# RF_Antenna_Power.net
KiCad netlist of a schematic drawn in Altium Designer
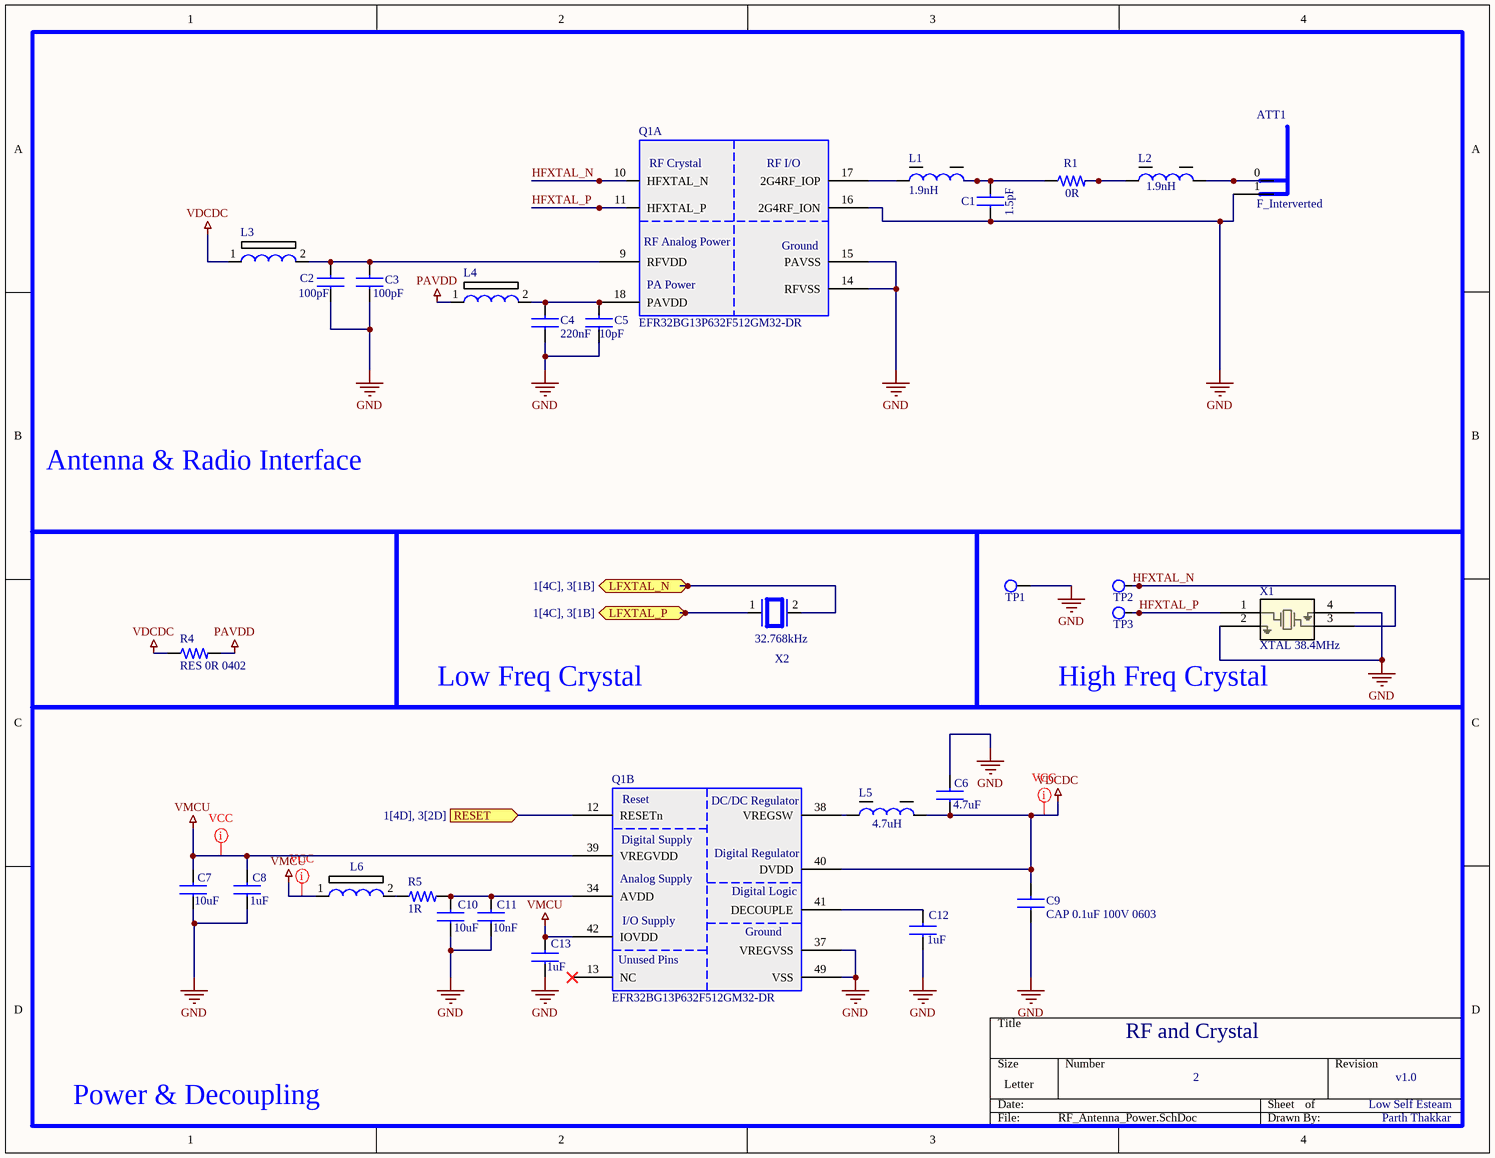
[diagram p0: RF_Antenna_Power.SchDoc]

(export (version "E")
  (design (tool "Eeschema 10.0.6"))
  (components
    (comp (ref "ATT1")
      (value "F_Interverted")
      (footprint "F_Inverted")
      (description "For 50Ohm impedence, Inverted F antenna")
      (libsource (lib "Keyboard_parts") (part "F_Interverted"))
    )
    (comp (ref "C1")
      (value "1.5pF")
      (footprint "Capacitor 0402")
      (fields
        (field (name "MANUFACTURER") "Murata")
        (field (name "MANUFACTURER PART NUMBER") "GJM1555C1H1R5WB01D")
        (field (name "Comment") "CAP 1.5pF 50V 0402")
      )
      (libsource (lib "Keyboard_parts") (part "CAP 1.5pF 50V 0402"))
    )
    (comp (ref "C2")
      (value "100pF")
      (footprint "Capacitor 0603")
      (fields
        (field (name "MANUFACTURER") "Murata")
        (field (name "MANUFACTURER PART NUMBER") "GCM1885C2A101JA16D")
        (field (name "Comment") "CAP 100pF 100V 0603")
      )
      (libsource (lib "Keyboard_parts") (part "CAP 100pF 100V 0603"))
    )
    (comp (ref "C3")
      (value "100pF")
      (footprint "Capacitor 0603")
      (fields
        (field (name "MANUFACTURER") "Murata")
        (field (name "MANUFACTURER PART NUMBER") "GCM1885C2A101JA16D")
        (field (name "Comment") "CAP 100pF 100V 0603")
      )
      (libsource (lib "Keyboard_parts") (part "CAP 100pF 100V 0603"))
    )
    (comp (ref "C4")
      (value "220nF")
      (footprint "Capacitor 0603")
      (fields
        (field (name "MANUFACTURER") "Murata")
        (field (name "MANUFACTURER PART NUMBER") "GRM188R71H224KAC4D")
        (field (name "Comment") "CAP 220nF 50V 0603")
      )
      (libsource (lib "Keyboard_parts") (part "CAP 220nF 50V 0603"))
    )
    (comp (ref "C5")
      (value "10pF")
      (footprint "Capacitor 0603")
      (fields
        (field (name "MANUFACTURER") "Murata")
        (field (name "MANUFACTURER PART NUMBER") "GRM1555C1H100FA01D")
        (field (name "Comment") "CAP 10pF 50V 0603")
      )
      (libsource (lib "Keyboard_parts") (part "CAP 10pF 50V 0603"))
    )
    (comp (ref "C6")
      (value "4.7uF")
      (footprint "Capacitor 0603")
      (fields
        (field (name "MANUFACTURER") "Murata")
        (field (name "MANUFACTURER PART NUMBER") "GRT188R61E475KE13D")
        (field (name "Comment") "CAP 4.7uF 25V 0603")
      )
      (libsource (lib "Keyboard_parts") (part "CAP 4.7uF 25V 0603"))
    )
    (comp (ref "C7")
      (value "10uF")
      (footprint "Capacitor 0603")
      (fields
        (field (name "MANUFACTURER") "Murata")
        (field (name "MANUFACTURER PART NUMBER") "GRM188R61A106ME69D")
        (field (name "Comment") "CAP 10uF 10V 0603")
      )
      (libsource (lib "Keyboard_parts") (part "CAP 10uF 10V 0603"))
    )
    (comp (ref "C8")
      (value "1uF")
      (footprint "Capacitor 0603")
      (fields
        (field (name "MANUFACTURER") "Murata")
        (field (name "MANUFACTURER PART NUMBER") "GRM188R61A105KA61D")
        (field (name "Comment") "CAP 1uF 10V 0603")
      )
      (libsource (lib "Keyboard_parts") (part "CAP 1uF 10V 0603"))
    )
    (comp (ref "C9")
      (value "CAP 0.1uF 100V 0603")
      (footprint "Capacitor 0603")
      (fields
        (field (name "MANUFACTURER") "Murata")
        (field (name "MANUFACTURER PART NUMBER") "GCM188R72A103KA37D")
      )
      (libsource (lib "Keyboard_parts") (part "CAP 0.1uF 100V 0603"))
    )
    (comp (ref "C10")
      (value "10uF")
      (footprint "Capacitor 0603")
      (fields
        (field (name "MANUFACTURER") "Murata")
        (field (name "MANUFACTURER PART NUMBER") "GRM188R61A106ME69D")
        (field (name "Comment") "CAP 10uF 10V 0603")
      )
      (libsource (lib "Keyboard_parts") (part "CAP 10uF 10V 0603"))
    )
    (comp (ref "C11")
      (value "10nF")
      (footprint "Capacitor 0603")
      (fields
        (field (name "MANUFACTURER") "Murata")
        (field (name "MANUFACTURER PART NUMBER") "GCM188R72A103KA37D")
        (field (name "Comment") "CAP 10nF 100V 0603")
      )
      (libsource (lib "Keyboard_parts") (part "CAP 10nF 100V 0603"))
    )
    (comp (ref "C12")
      (value "1uF")
      (footprint "Capacitor 0603")
      (fields
        (field (name "MANUFACTURER") "Murata")
        (field (name "MANUFACTURER PART NUMBER") "GRM188R61A105KA61D")
        (field (name "Comment") "CAP 1uF 10V 0603")
      )
      (libsource (lib "Keyboard_parts") (part "CAP 1uF 10V 0603"))
    )
    (comp (ref "C13")
      (value "1uF")
      (footprint "Capacitor 0603")
      (fields
        (field (name "MANUFACTURER") "Murata")
        (field (name "MANUFACTURER PART NUMBER") "GRM188R61A105KA61D")
        (field (name "Comment") "CAP 1uF 10V 0603")
      )
      (libsource (lib "Keyboard_parts") (part "CAP 1uF 10V 0603"))
    )
    (comp (ref "L1")
      (value "1.9nH")
      (footprint "Ferrite 0402")
      (description "Inductor Chip 1.9nH 0.3nH Tolerance 2-Pin 0402 Paper T/R")
      (fields
        (field (name "MANUFACTURER") "Murata")
        (field (name "MANUFACTURER PART NUMBER") "LQG15WZ1N9S02D")
      )
      (libsource (lib "Keyboard_parts") (part "IND 1.9nH 0402"))
    )
    (comp (ref "L2")
      (value "1.9nH")
      (footprint "Ferrite 0402")
      (description "Inductor Chip 1.9nH 0.3nH Tolerance 2-Pin 0402 Paper T/R")
      (fields
        (field (name "MANUFACTURER") "Murata")
        (field (name "MANUFACTURER PART NUMBER") "LQG15WZ1N9S02D")
      )
      (libsource (lib "Keyboard_parts") (part "IND 1.9nH 0402"))
    )
    (comp (ref "L3")
      (value "Ferrite Bead 600(601) 1LN")
      (footprint "Ferrite 0603")
      (description "RFVDD, PAVDD, EFR")
      (fields
        (field (name "MANUFACTURER") "Murata")
        (field (name "MANUFACTURER PART NUMBER") "BLM18AG601SN1D")
      )
      (libsource (lib "Keyboard_parts") (part "Ferrite Bead 600(601) 1LN"))
    )
    (comp (ref "L4")
      (value "Ferrite Bead 600(601) 1LN")
      (footprint "Ferrite 0603")
      (description "RFVDD, PAVDD, EFR")
      (fields
        (field (name "MANUFACTURER") "Murata")
        (field (name "MANUFACTURER PART NUMBER") "BLM18AG601SN1D")
      )
      (libsource (lib "Keyboard_parts") (part "Ferrite Bead 600(601) 1LN"))
    )
    (comp (ref "L5")
      (value "IND 4.7uH 1515")
      (footprint "IND 22uH (1.6x4.3)")
      (description "General Purpose Inductor, 4.7uH, 30%, 1 Element, Ferrite-Core, SMD, 1515")
      (fields
        (field (name "MANUFACTURER") "Wurth Electronics")
        (field (name "MANUFACTURER PART NUMBER") "744031004")
        (field (name "INDUCTANCE-NOM (L)") "4.7uH")
      )
      (libsource (lib "Keyboard_parts") (part "IND 4.7uH 1515"))
    )
    (comp (ref "L6")
      (value "Farrite Bead 102(1k)")
      (footprint "Ferrite 0402")
      (description "Ferrite Chip, 1 Function(s), 0.05A, 2 Pin(s)")
      (fields
        (field (name "MANUFACTURER") "Wurth Electronics")
        (field (name "MANUFACTURER PART NUMBER") "742841210")
      )
      (libsource (lib "Keyboard_parts") (part "Farrite Bead 102(1k)"))
    )
    (comp (ref "Q1")
      (value "EFR32BG13P632F512GM32-DR")
      (footprint "EFR32BG")
      (description "BLue Gecko")
      (fields (field (name "MANUFACTURER") "Silicon Labs"))
      (libsource (lib "Keyboard_parts") (part "EFR32BG13P632F512GM32-DR"))
    )
    (comp (ref "R1")
      (value "0R")
      (footprint "Resistor 0402")
      (description "Metal Glaze/thick Film, 0.0625W, 0ohm, Surface Mount, 0402")
      (fields
        (field (name "MANUFACTURER") "Yageo")
        (field (name "MANUFACTURER PART NUMBER") "RC0402JR-070RL")
      )
      (libsource (lib "Keyboard_parts") (part "RES 0R 0402"))
    )
    (comp (ref "R4")
      (value "RES 0R 0402")
      (footprint "Resistor 0402")
      (description "Metal Glaze/thick Film, 0.0625W, 0ohm, Surface Mount, 0402")
      (fields
        (field (name "MANUFACTURER") "Yageo")
        (field (name "MANUFACTURER PART NUMBER") "RC0402JR-070RL")
      )
      (libsource (lib "Keyboard_parts") (part "RES 0R 0402"))
    )
    (comp (ref "R5")
      (value "1R")
      (footprint "Resistor 0603")
      (fields
        (field (name "MANUFACTURER") "Yageo")
        (field (name "MANUFACTURER PART NUMBER") "RC0603FR-071RL")
        (field (name "TOLERANCE") "1%")
      )
      (libsource (lib "Keyboard_parts") (part "RES 1R 0603"))
    )
    (comp (ref "TP1")
      (value "Test point")
      (footprint "Test Point")
      (libsource (lib "Keyboard_parts") (part "Test point"))
    )
    (comp (ref "TP2")
      (value "Test point")
      (footprint "Test Point")
      (libsource (lib "Keyboard_parts") (part "Test point"))
    )
    (comp (ref "TP3")
      (value "Test point")
      (footprint "Test Point")
      (libsource (lib "Keyboard_parts") (part "Test point"))
    )
    (comp (ref "X1")
      (value "XTAL 38.4MHz")
      (footprint "XTAL 38.4MHz")
      (description "Crystal 38.4000MHZ 10PF SMD")
      (fields
        (field (name "MANUFACTURER") "Murata")
        (field (name "MANUFACTURER PART NUMBER") "XRCGB38M400F1S3JR0")
      )
      (libsource (lib "Keyboard_parts") (part "XTAL 38.4MHz"))
    )
    (comp (ref "X2")
      (value "32.768kHz")
      (footprint "XTAL_32.768KHZ-T")
      (description "Parallel - Fundamental Quartz Crystal, 0.032768MHz Nom")
      (fields
        (field (name "MANUFACTURER") "Abracon")
        (field (name "MANUFACTURER PART NUMBER") "ABS07-32.768KHZ-T")
      )
      (libsource (lib "Keyboard_parts") (part "XTAL 32.768kHz"))
    )
  )
  (nets
    (net (code "1") (name "/HFXTAL_N") (class "Default")
      (node (ref "Q1") (pin "10") (pinfunction "HFXTAL_N_10") (pintype "passive"))
      (node (ref "TP2") (pin "1") (pinfunction "1_1") (pintype "passive"))
      (node (ref "X1") (pin "3") (pinfunction "3_3") (pintype "passive"))
    )
    (net (code "2") (name "/HFXTAL_P") (class "Default")
      (node (ref "Q1") (pin "11") (pinfunction "HFXTAL_P_11") (pintype "passive"))
      (node (ref "TP3") (pin "1") (pinfunction "1_1") (pintype "passive"))
      (node (ref "X1") (pin "1") (pinfunction "1_1") (pintype "passive"))
    )
    (net (code "3") (name "/LFXTAL_N") (class "Default")
      (node (ref "X2") (pin "2") (pinfunction "2_2") (pintype "passive"))
    )
    (net (code "4") (name "/LFXTAL_P") (class "Default")
      (node (ref "X2") (pin "1") (pinfunction "1_1") (pintype "passive"))
    )
    (net (code "5") (name "/RESET") (class "Default")
      (node (ref "Q1") (pin "12") (pinfunction "RESETn_12") (pintype "passive"))
    )
    (net (code "6") (name "GND") (class "Default")
      (node (ref "ATT1") (pin "1") (pinfunction "GND_1") (pintype "passive"))
      (node (ref "C1") (pin "2") (pinfunction "2_2") (pintype "passive"))
      (node (ref "C10") (pin "2") (pinfunction "2_2") (pintype "passive"))
      (node (ref "C11") (pin "2") (pinfunction "2_2") (pintype "passive"))
      (node (ref "C12") (pin "2") (pinfunction "2_2") (pintype "passive"))
      (node (ref "C13") (pin "2") (pinfunction "2_2") (pintype "passive"))
      (node (ref "C2") (pin "2") (pinfunction "2_2") (pintype "passive"))
      (node (ref "C3") (pin "2") (pinfunction "2_2") (pintype "passive"))
      (node (ref "C4") (pin "2") (pinfunction "2_2") (pintype "passive"))
      (node (ref "C5") (pin "2") (pinfunction "2_2") (pintype "passive"))
      (node (ref "C6") (pin "2") (pinfunction "2_2") (pintype "passive"))
      (node (ref "C7") (pin "2") (pinfunction "2_2") (pintype "passive"))
      (node (ref "C8") (pin "2") (pinfunction "2_2") (pintype "passive"))
      (node (ref "C9") (pin "2") (pinfunction "2_2") (pintype "passive"))
      (node (ref "Q1") (pin "14") (pinfunction "RFVSS_14") (pintype "power_in"))
      (node (ref "Q1") (pin "15") (pinfunction "PAVSS_15") (pintype "power_in"))
      (node (ref "Q1") (pin "16") (pinfunction "2G4RF_ION_16") (pintype "passive"))
      (node (ref "Q1") (pin "37") (pinfunction "VREGVSS_37") (pintype "power_in"))
      (node (ref "Q1") (pin "49") (pinfunction "VSS_49") (pintype "power_in"))
      (node (ref "TP1") (pin "1") (pinfunction "1_1") (pintype "passive"))
      (node (ref "X1") (pin "2") (pinfunction "2_2") (pintype "passive"))
      (node (ref "X1") (pin "4") (pinfunction "4_4") (pintype "passive"))
    )
    (net (code "7") (name "Net-(ATT1-FEED)") (class "Default")
      (node (ref "ATT1") (pin "0") (pinfunction "FEED_0") (pintype "passive"))
      (node (ref "L2") (pin "2") (pinfunction "2_2") (pintype "passive"))
    )
    (net (code "8") (name "Net-(C1-Pad1)") (class "Default")
      (node (ref "C1") (pin "1") (pinfunction "1_1") (pintype "passive"))
      (node (ref "L1") (pin "2") (pinfunction "2_2") (pintype "passive"))
      (node (ref "R1") (pin "1") (pinfunction "1_1") (pintype "passive"))
    )
    (net (code "9") (name "Net-(L2-Pad1)") (class "Default")
      (node (ref "L2") (pin "1") (pinfunction "1_1") (pintype "passive"))
      (node (ref "R1") (pin "2") (pinfunction "2_2") (pintype "passive"))
    )
    (net (code "10") (name "Net-(L6-Pad2)") (class "Default")
      (node (ref "L6") (pin "2") (pinfunction "2_2") (pintype "passive"))
      (node (ref "R5") (pin "1") (pinfunction "1_1") (pintype "passive"))
    )
    (net (code "11") (name "Net-(Q1A-2G4RF_IOP)") (class "Default")
      (node (ref "L1") (pin "1") (pinfunction "1_1") (pintype "passive"))
      (node (ref "Q1") (pin "17") (pinfunction "2G4RF_IOP_17") (pintype "passive"))
    )
    (net (code "12") (name "Net-(Q1A-PAVDD)") (class "Default")
      (node (ref "C4") (pin "1") (pinfunction "1_1") (pintype "passive"))
      (node (ref "C5") (pin "1") (pinfunction "1_1") (pintype "passive"))
      (node (ref "L4") (pin "2") (pinfunction "2_2") (pintype "passive"))
      (node (ref "Q1") (pin "18") (pinfunction "PAVDD_18") (pintype "power_in"))
    )
    (net (code "13") (name "Net-(Q1A-RFVDD)") (class "Default")
      (node (ref "C2") (pin "1") (pinfunction "1_1") (pintype "passive"))
      (node (ref "C3") (pin "1") (pinfunction "1_1") (pintype "passive"))
      (node (ref "L3") (pin "2") (pinfunction "2_2") (pintype "passive"))
      (node (ref "Q1") (pin "9") (pinfunction "RFVDD_9") (pintype "power_in"))
    )
    (net (code "14") (name "Net-(Q1B-AVDD)") (class "Default")
      (node (ref "C10") (pin "1") (pinfunction "1_1") (pintype "passive"))
      (node (ref "C11") (pin "1") (pinfunction "1_1") (pintype "passive"))
      (node (ref "Q1") (pin "34") (pinfunction "AVDD_34") (pintype "power_in"))
      (node (ref "R5") (pin "2") (pinfunction "2_2") (pintype "passive"))
    )
    (net (code "15") (name "Net-(Q1B-DECOUPLE)") (class "Default")
      (node (ref "C12") (pin "1") (pinfunction "1_1") (pintype "passive"))
      (node (ref "Q1") (pin "41") (pinfunction "DECOUPLE_41") (pintype "passive"))
    )
    (net (code "16") (name "Net-(Q1B-VREGSW)") (class "Default")
      (node (ref "L5") (pin "1") (pinfunction "1_1") (pintype "passive"))
      (node (ref "Q1") (pin "38") (pinfunction "VREGSW_38") (pintype "power_in"))
    )
    (net (code "17") (name "PAVDD") (class "Default")
      (node (ref "L4") (pin "1") (pinfunction "1_1") (pintype "passive"))
      (node (ref "R4") (pin "2") (pinfunction "2_2") (pintype "passive"))
    )
    (net (code "18") (name "VDCDC") (class "Default")
      (node (ref "C6") (pin "1") (pinfunction "1_1") (pintype "passive"))
      (node (ref "C9") (pin "1") (pinfunction "1_1") (pintype "passive"))
      (node (ref "L3") (pin "1") (pinfunction "1_1") (pintype "passive"))
      (node (ref "L5") (pin "2") (pinfunction "2_2") (pintype "passive"))
      (node (ref "Q1") (pin "40") (pinfunction "DVDD_40") (pintype "power_in"))
      (node (ref "R4") (pin "1") (pinfunction "1_1") (pintype "passive"))
    )
    (net (code "19") (name "VMCU") (class "Default")
      (node (ref "C13") (pin "1") (pinfunction "1_1") (pintype "passive"))
      (node (ref "C7") (pin "1") (pinfunction "1_1") (pintype "passive"))
      (node (ref "C8") (pin "1") (pinfunction "1_1") (pintype "passive"))
      (node (ref "L6") (pin "1") (pinfunction "1_1") (pintype "passive"))
      (node (ref "Q1") (pin "39") (pinfunction "VREGVDD_39") (pintype "power_in"))
      (node (ref "Q1") (pin "42") (pinfunction "IOVDD_42") (pintype "power_in"))
    )
    (net (code "20") (name "unconnected-(Q1B-NC-Pad13)") (class "Default")
      (node (ref "Q1") (pin "13") (pinfunction "NC_13") (pintype "passive+no_connect"))
    )
  )
)
